# firstboard.net
KiCad netlist of a schematic drawn in EAGLE
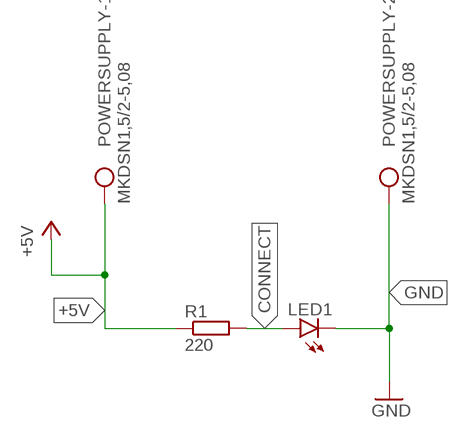
[diagram p0: schematic, sheet 1]

(export (version "E")
  (design (tool "Eeschema 10.0.6"))
  (components
    (comp (ref "LED1")
      (value "LED3MM")
      (footprint "eagle-import:LED3MM")
      (libsource (lib "eagle-import") (part "LED3MM"))
    )
    (comp (ref "POWERSUPPLY")
      (value "MKDSN1,5/2-5,08")
      (footprint "eagle-import:MKDSN1,5_2-5,08")
      (libsource (lib "eagle-import") (part "MKDSN1,5/2-5,08"))
    )
    (comp (ref "R1")
      (value "220")
      (footprint "eagle-import:R0805")
      (libsource (lib "eagle-import") (part "R-EU_R0805"))
    )
  )
  (nets
    (net (code "1") (name "+5V") (class "Default")
      (node (ref "POWERSUPPLY") (pin "1") (pinfunction "KL_1") (pintype "passive"))
      (node (ref "R1") (pin "1") (pinfunction "1_1") (pintype "passive"))
    )
    (net (code "2") (name "CONNECT") (class "Default")
      (node (ref "LED1") (pin "A") (pinfunction "A_A") (pintype "passive"))
      (node (ref "R1") (pin "2") (pinfunction "2_2") (pintype "passive"))
    )
    (net (code "3") (name "GND") (class "Default")
      (node (ref "LED1") (pin "K") (pinfunction "C_K") (pintype "passive"))
      (node (ref "POWERSUPPLY") (pin "2") (pinfunction "KL_2") (pintype "passive"))
    )
  )
)
